# working.net
KiCad netlist of a schematic drawn in EAGLE
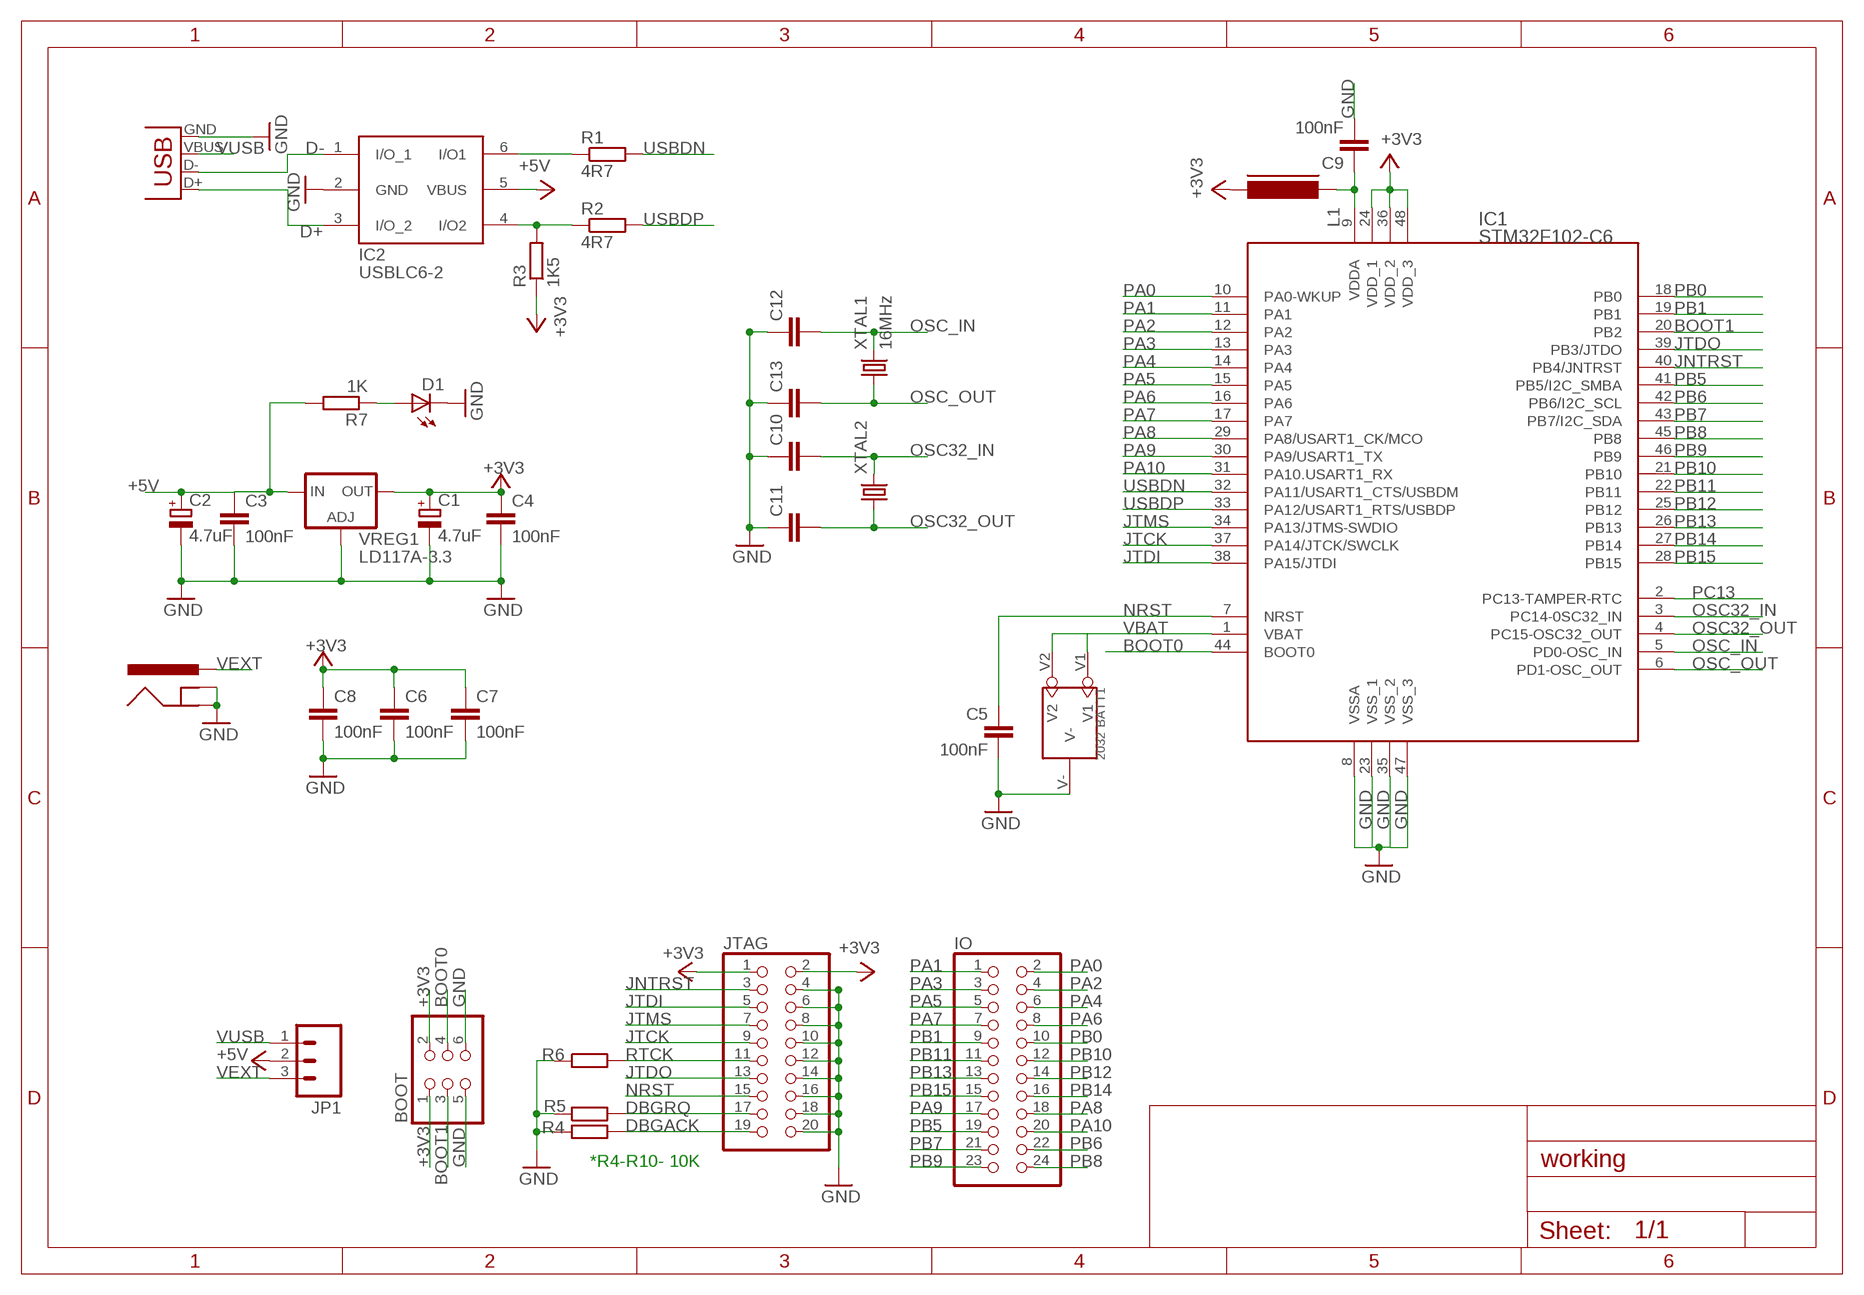
[diagram p0: schematic, sheet 1]

(export (version "E")
  (design (tool "Eeschema 10.0.6"))
  (components
    (comp (ref "BATT1")
      (value "2032")
      (footprint "eagle-import:2032")
      (libsource (lib "eagle-import") (part "2032"))
    )
    (comp (ref "BOOT")
      (value "PINHD-2X3")
      (footprint "eagle-import:2X03")
      (libsource (lib "eagle-import") (part "PINHD-2X3"))
    )
    (comp (ref "C1")
      (value "4.7uF")
      (footprint "eagle-import:SMC_A")
      (libsource (lib "eagle-import") (part "CAP_POLSMC_A"))
    )
    (comp (ref "C2")
      (value "4.7uF")
      (footprint "eagle-import:SMC_A")
      (libsource (lib "eagle-import") (part "CAP_POLSMC_A"))
    )
    (comp (ref "C3")
      (value "100nF")
      (footprint "eagle-import:C0805")
      (libsource (lib "eagle-import") (part "C-EUC0805"))
    )
    (comp (ref "C4")
      (value "100nF")
      (footprint "eagle-import:C0805")
      (libsource (lib "eagle-import") (part "C-EUC0805"))
    )
    (comp (ref "C5")
      (value "100nF")
      (footprint "eagle-import:C0805")
      (libsource (lib "eagle-import") (part "C-EUC0805"))
    )
    (comp (ref "C6")
      (value "100nF")
      (footprint "eagle-import:C0805")
      (libsource (lib "eagle-import") (part "C-EUC0805"))
    )
    (comp (ref "C7")
      (value "100nF")
      (footprint "eagle-import:C0805")
      (libsource (lib "eagle-import") (part "C-EUC0805"))
    )
    (comp (ref "C8")
      (value "100nF")
      (footprint "eagle-import:C0805")
      (libsource (lib "eagle-import") (part "C-EUC0805"))
    )
    (comp (ref "C9")
      (value "100nF")
      (footprint "eagle-import:C0805")
      (libsource (lib "eagle-import") (part "C-EUC0805"))
    )
    (comp (ref "C10")
      (value "CAPC805")
      (footprint "eagle-import:C805")
      (libsource (lib "eagle-import") (part "CAPC805"))
    )
    (comp (ref "C11")
      (value "CAPC805")
      (footprint "eagle-import:C805")
      (libsource (lib "eagle-import") (part "CAPC805"))
    )
    (comp (ref "C12")
      (value "CAPC805")
      (footprint "eagle-import:C805")
      (libsource (lib "eagle-import") (part "CAPC805"))
    )
    (comp (ref "C13")
      (value "CAPC805")
      (footprint "eagle-import:C805")
      (libsource (lib "eagle-import") (part "CAPC805"))
    )
    (comp (ref "D1")
      (value "LEDCHIPLED_0805")
      (footprint "eagle-import:CHIPLED_0805")
      (libsource (lib "eagle-import") (part "LEDCHIPLED_0805"))
    )
    (comp (ref "IC1")
      (value "STM32F102-C6")
      (footprint "eagle-import:LQFP48")
      (libsource (lib "eagle-import") (part "STM32"))
    )
    (comp (ref "IC2")
      (value "USBLC6-2")
      (footprint "eagle-import:SOT23-6L")
      (libsource (lib "eagle-import") (part "USBLC6-2"))
    )
    (comp (ref "IO")
      (value "PINHD-2X12")
      (footprint "eagle-import:2X12")
      (libsource (lib "eagle-import") (part "PINHD-2X12"))
    )
    (comp (ref "JP1")
      (value "M03PTH")
      (footprint "eagle-import:1X03")
      (libsource (lib "eagle-import") (part "M03PTH"))
    )
    (comp (ref "JTAG")
      (value "PINHD-2X10")
      (footprint "eagle-import:2X10")
      (libsource (lib "eagle-import") (part "PINHD-2X10"))
    )
    (comp (ref "L1")
      (value "FERRITE_BEAD805")
      (footprint "eagle-import:FB805")
      (libsource (lib "eagle-import") (part "FERRITE_BEAD805"))
    )
    (comp (ref "R1")
      (value "4R7")
      (footprint "eagle-import:R0805")
      (libsource (lib "eagle-import") (part "R-EU_R0805"))
    )
    (comp (ref "R2")
      (value "4R7")
      (footprint "eagle-import:R0805")
      (libsource (lib "eagle-import") (part "R-EU_R0805"))
    )
    (comp (ref "R3")
      (value "1K5")
      (footprint "eagle-import:R0805")
      (libsource (lib "eagle-import") (part "R-EU_R0805"))
    )
    (comp (ref "R4")
      (value "R-EU_R0805")
      (footprint "eagle-import:R0805")
      (libsource (lib "eagle-import") (part "R-EU_R0805"))
    )
    (comp (ref "R5")
      (value "R-EU_R0805")
      (footprint "eagle-import:R0805")
      (libsource (lib "eagle-import") (part "R-EU_R0805"))
    )
    (comp (ref "R6")
      (value "R-EU_R0805")
      (footprint "eagle-import:R0805")
      (libsource (lib "eagle-import") (part "R-EU_R0805"))
    )
    (comp (ref "R7")
      (value "1K")
      (footprint "eagle-import:R0805")
      (libsource (lib "eagle-import") (part "R-EU_R0805"))
    )
    (comp (ref "U$1")
      (value "POWER_JACKSMD")
      (footprint "eagle-import:POWER_JACK_SMD")
      (libsource (lib "eagle-import") (part "POWER_JACKSMD"))
    )
    (comp (ref "USB")
      (value "USBMINIB")
      (footprint "eagle-import:USB-MINIB")
      (libsource (lib "eagle-import") (part "USBMINIB"))
    )
    (comp (ref "VREG1")
      (value "LD117A-3.3")
      (footprint "eagle-import:SOT223")
      (libsource (lib "eagle-import") (part "LD117A?S12TR"))
    )
    (comp (ref "XTAL1")
      (value "16MHz")
      (footprint "eagle-import:HC49UP")
      (libsource (lib "eagle-import") (part "CRYSTALHC49UP"))
    )
    (comp (ref "XTAL2")
      (value "CRYSTALMM20SS")
      (footprint "eagle-import:MM20SS")
      (libsource (lib "eagle-import") (part "CRYSTALMM20SS"))
    )
  )
  (nets
    (net (code "1") (name "+3V3") (class "Default")
      (node (ref "BOOT") (pin "1") (pinfunction "1_1") (pintype "passive"))
      (node (ref "BOOT") (pin "2") (pinfunction "2_2") (pintype "passive"))
      (node (ref "C1") (pin "+") (pinfunction "+_+") (pintype "passive"))
      (node (ref "C4") (pin "1") (pinfunction "1_1") (pintype "passive"))
      (node (ref "C6") (pin "1") (pinfunction "1_1") (pintype "passive"))
      (node (ref "C7") (pin "1") (pinfunction "1_1") (pintype "passive"))
      (node (ref "C8") (pin "1") (pinfunction "1_1") (pintype "passive"))
      (node (ref "IC1") (pin "24") (pinfunction "VDD_1_24") (pintype "power_in"))
      (node (ref "IC1") (pin "36") (pinfunction "VDD_2_36") (pintype "power_in"))
      (node (ref "IC1") (pin "48") (pinfunction "VDD_3_48") (pintype "power_in"))
      (node (ref "JTAG") (pin "1") (pinfunction "1_1") (pintype "passive"))
      (node (ref "JTAG") (pin "2") (pinfunction "2_2") (pintype "passive"))
      (node (ref "L1") (pin "2") (pinfunction "2_2") (pintype "passive"))
      (node (ref "R3") (pin "1") (pinfunction "1_1") (pintype "passive"))
      (node (ref "VREG1") (pin "4") (pinfunction "OUT_4") (pintype "passive"))
    )
    (net (code "2") (name "+5V") (class "Default")
      (node (ref "C2") (pin "+") (pinfunction "+_+") (pintype "passive"))
      (node (ref "C3") (pin "1") (pinfunction "1_1") (pintype "passive"))
      (node (ref "IC2") (pin "5") (pinfunction "VBUS_5") (pintype "bidirectional"))
      (node (ref "JP1") (pin "2") (pinfunction "2_2") (pintype "passive"))
      (node (ref "R7") (pin "2") (pinfunction "2_2") (pintype "passive"))
      (node (ref "VREG1") (pin "3") (pinfunction "IN_3") (pintype "input"))
    )
    (net (code "3") (name "/BOOT0") (class "Default")
      (node (ref "BOOT") (pin "4") (pinfunction "4_4") (pintype "passive"))
      (node (ref "IC1") (pin "44") (pinfunction "BOOT0_44") (pintype "bidirectional"))
    )
    (net (code "4") (name "/BOOT1") (class "Default")
      (node (ref "BOOT") (pin "3") (pinfunction "3_3") (pintype "passive"))
      (node (ref "IC1") (pin "20") (pinfunction "PB2_20") (pintype "bidirectional"))
    )
    (net (code "5") (name "/D+") (class "Default")
      (node (ref "IC2") (pin "3") (pinfunction "I/O_2_3") (pintype "bidirectional"))
      (node (ref "USB") (pin "D+") (pinfunction "D+_D+") (pintype "bidirectional"))
    )
    (net (code "6") (name "/D-") (class "Default")
      (node (ref "IC2") (pin "1") (pinfunction "I/O_1_1") (pintype "bidirectional"))
      (node (ref "USB") (pin "D-") (pinfunction "D-_D-") (pintype "bidirectional"))
    )
    (net (code "7") (name "/DBGACK") (class "Default")
      (node (ref "JTAG") (pin "19") (pinfunction "19_19") (pintype "passive"))
      (node (ref "R4") (pin "2") (pinfunction "2_2") (pintype "passive"))
    )
    (net (code "8") (name "/DBGRQ") (class "Default")
      (node (ref "JTAG") (pin "17") (pinfunction "17_17") (pintype "passive"))
      (node (ref "R5") (pin "2") (pinfunction "2_2") (pintype "passive"))
    )
    (net (code "9") (name "/JNTRST") (class "Default")
      (node (ref "IC1") (pin "40") (pinfunction "PB4/JNTRST_40") (pintype "bidirectional"))
      (node (ref "JTAG") (pin "3") (pinfunction "3_3") (pintype "passive"))
    )
    (net (code "10") (name "/JTCK") (class "Default")
      (node (ref "IC1") (pin "37") (pinfunction "PA14/JTCK/SWCLK_37") (pintype "bidirectional"))
      (node (ref "JTAG") (pin "9") (pinfunction "9_9") (pintype "passive"))
    )
    (net (code "11") (name "/JTDI") (class "Default")
      (node (ref "IC1") (pin "38") (pinfunction "PA15/JTDI_38") (pintype "bidirectional"))
      (node (ref "JTAG") (pin "5") (pinfunction "5_5") (pintype "passive"))
    )
    (net (code "12") (name "/JTDO") (class "Default")
      (node (ref "IC1") (pin "39") (pinfunction "PB3/JTDO_39") (pintype "bidirectional"))
      (node (ref "JTAG") (pin "13") (pinfunction "13_13") (pintype "passive"))
    )
    (net (code "13") (name "/JTMS") (class "Default")
      (node (ref "IC1") (pin "34") (pinfunction "PA13/JTMS-SWDIO_34") (pintype "bidirectional"))
      (node (ref "JTAG") (pin "7") (pinfunction "7_7") (pintype "passive"))
    )
    (net (code "14") (name "/NRST") (class "Default")
      (node (ref "C5") (pin "1") (pinfunction "1_1") (pintype "passive"))
      (node (ref "IC1") (pin "7") (pinfunction "NRST_7") (pintype "bidirectional"))
      (node (ref "JTAG") (pin "15") (pinfunction "15_15") (pintype "passive"))
    )
    (net (code "15") (name "/OSC32_IN") (class "Default")
      (node (ref "C10") (pin "2") (pinfunction "2_2") (pintype "passive"))
      (node (ref "IC1") (pin "3") (pinfunction "PC14-0SC32_IN_3") (pintype "bidirectional"))
      (node (ref "XTAL2") (pin "4") (pinfunction "2_4") (pintype "passive"))
    )
    (net (code "16") (name "/OSC32_OUT") (class "Default")
      (node (ref "C11") (pin "2") (pinfunction "2_2") (pintype "passive"))
      (node (ref "IC1") (pin "4") (pinfunction "PC15-OSC32_OUT_4") (pintype "bidirectional"))
      (node (ref "XTAL2") (pin "1") (pinfunction "1_1") (pintype "passive"))
    )
    (net (code "17") (name "/OSC_IN") (class "Default")
      (node (ref "C12") (pin "2") (pinfunction "2_2") (pintype "passive"))
      (node (ref "IC1") (pin "5") (pinfunction "PD0-OSC_IN_5") (pintype "bidirectional"))
      (node (ref "XTAL1") (pin "2") (pinfunction "2_2") (pintype "passive"))
    )
    (net (code "18") (name "/OSC_OUT") (class "Default")
      (node (ref "C13") (pin "2") (pinfunction "2_2") (pintype "passive"))
      (node (ref "IC1") (pin "6") (pinfunction "PD1-OSC_OUT_6") (pintype "bidirectional"))
      (node (ref "XTAL1") (pin "1") (pinfunction "1_1") (pintype "passive"))
    )
    (net (code "19") (name "/PA0") (class "Default")
      (node (ref "IC1") (pin "10") (pinfunction "PA0-WKUP_10") (pintype "bidirectional"))
      (node (ref "IO") (pin "2") (pinfunction "2_2") (pintype "passive"))
    )
    (net (code "20") (name "/PA1") (class "Default")
      (node (ref "IC1") (pin "11") (pinfunction "PA1_11") (pintype "bidirectional"))
      (node (ref "IO") (pin "1") (pinfunction "1_1") (pintype "passive"))
    )
    (net (code "21") (name "/PA2") (class "Default")
      (node (ref "IC1") (pin "12") (pinfunction "PA2_12") (pintype "bidirectional"))
      (node (ref "IO") (pin "4") (pinfunction "4_4") (pintype "passive"))
    )
    (net (code "22") (name "/PA3") (class "Default")
      (node (ref "IC1") (pin "13") (pinfunction "PA3_13") (pintype "bidirectional"))
      (node (ref "IO") (pin "3") (pinfunction "3_3") (pintype "passive"))
    )
    (net (code "23") (name "/PA4") (class "Default")
      (node (ref "IC1") (pin "14") (pinfunction "PA4_14") (pintype "bidirectional"))
      (node (ref "IO") (pin "6") (pinfunction "6_6") (pintype "passive"))
    )
    (net (code "24") (name "/PA5") (class "Default")
      (node (ref "IC1") (pin "15") (pinfunction "PA5_15") (pintype "bidirectional"))
      (node (ref "IO") (pin "5") (pinfunction "5_5") (pintype "passive"))
    )
    (net (code "25") (name "/PA6") (class "Default")
      (node (ref "IC1") (pin "16") (pinfunction "PA6_16") (pintype "bidirectional"))
      (node (ref "IO") (pin "8") (pinfunction "8_8") (pintype "passive"))
    )
    (net (code "26") (name "/PA7") (class "Default")
      (node (ref "IC1") (pin "17") (pinfunction "PA7_17") (pintype "bidirectional"))
      (node (ref "IO") (pin "7") (pinfunction "7_7") (pintype "passive"))
    )
    (net (code "27") (name "/PA8") (class "Default")
      (node (ref "IC1") (pin "29") (pinfunction "PA8/USART1_CK/MCO_29") (pintype "bidirectional"))
      (node (ref "IO") (pin "18") (pinfunction "18_18") (pintype "passive"))
    )
    (net (code "28") (name "/PA9") (class "Default")
      (node (ref "IC1") (pin "30") (pinfunction "PA9/USART1_TX_30") (pintype "bidirectional"))
      (node (ref "IO") (pin "17") (pinfunction "17_17") (pintype "passive"))
    )
    (net (code "29") (name "/PA10") (class "Default")
      (node (ref "IC1") (pin "31") (pinfunction "PA10.USART1_RX_31") (pintype "bidirectional"))
      (node (ref "IO") (pin "20") (pinfunction "20_20") (pintype "passive"))
    )
    (net (code "30") (name "/PB0") (class "Default")
      (node (ref "IC1") (pin "18") (pinfunction "PB0_18") (pintype "bidirectional"))
      (node (ref "IO") (pin "10") (pinfunction "10_10") (pintype "passive"))
    )
    (net (code "31") (name "/PB1") (class "Default")
      (node (ref "IC1") (pin "19") (pinfunction "PB1_19") (pintype "bidirectional"))
      (node (ref "IO") (pin "9") (pinfunction "9_9") (pintype "passive"))
    )
    (net (code "32") (name "/PB5") (class "Default")
      (node (ref "IC1") (pin "41") (pinfunction "PB5/I2C_SMBA_41") (pintype "bidirectional"))
      (node (ref "IO") (pin "19") (pinfunction "19_19") (pintype "passive"))
    )
    (net (code "33") (name "/PB6") (class "Default")
      (node (ref "IC1") (pin "42") (pinfunction "PB6/I2C_SCL_42") (pintype "bidirectional"))
      (node (ref "IO") (pin "22") (pinfunction "22_22") (pintype "passive"))
    )
    (net (code "34") (name "/PB7") (class "Default")
      (node (ref "IC1") (pin "43") (pinfunction "PB7/I2C_SDA_43") (pintype "bidirectional"))
      (node (ref "IO") (pin "21") (pinfunction "21_21") (pintype "passive"))
    )
    (net (code "35") (name "/PB8") (class "Default")
      (node (ref "IC1") (pin "45") (pinfunction "PB8_45") (pintype "bidirectional"))
      (node (ref "IO") (pin "24") (pinfunction "24_24") (pintype "passive"))
    )
    (net (code "36") (name "/PB9") (class "Default")
      (node (ref "IC1") (pin "46") (pinfunction "PB9_46") (pintype "bidirectional"))
      (node (ref "IO") (pin "23") (pinfunction "23_23") (pintype "passive"))
    )
    (net (code "37") (name "/PB10") (class "Default")
      (node (ref "IC1") (pin "21") (pinfunction "PB10_21") (pintype "bidirectional"))
      (node (ref "IO") (pin "12") (pinfunction "12_12") (pintype "passive"))
    )
    (net (code "38") (name "/PB11") (class "Default")
      (node (ref "IC1") (pin "22") (pinfunction "PB11_22") (pintype "bidirectional"))
      (node (ref "IO") (pin "11") (pinfunction "11_11") (pintype "passive"))
    )
    (net (code "39") (name "/PB12") (class "Default")
      (node (ref "IC1") (pin "25") (pinfunction "PB12_25") (pintype "bidirectional"))
      (node (ref "IO") (pin "14") (pinfunction "14_14") (pintype "passive"))
    )
    (net (code "40") (name "/PB13") (class "Default")
      (node (ref "IC1") (pin "26") (pinfunction "PB13_26") (pintype "bidirectional"))
      (node (ref "IO") (pin "13") (pinfunction "13_13") (pintype "passive"))
    )
    (net (code "41") (name "/PB14") (class "Default")
      (node (ref "IC1") (pin "27") (pinfunction "PB14_27") (pintype "bidirectional"))
      (node (ref "IO") (pin "16") (pinfunction "16_16") (pintype "passive"))
    )
    (net (code "42") (name "/PB15") (class "Default")
      (node (ref "IC1") (pin "28") (pinfunction "PB15_28") (pintype "bidirectional"))
      (node (ref "IO") (pin "15") (pinfunction "15_15") (pintype "passive"))
    )
    (net (code "43") (name "/PC13") (class "Default")
      (node (ref "IC1") (pin "2") (pinfunction "PC13-TAMPER-RTC_2") (pintype "bidirectional"))
    )
    (net (code "44") (name "/RTCK") (class "Default")
      (node (ref "JTAG") (pin "11") (pinfunction "11_11") (pintype "passive"))
      (node (ref "R6") (pin "2") (pinfunction "2_2") (pintype "passive"))
    )
    (net (code "45") (name "/USBDN") (class "Default")
      (node (ref "IC1") (pin "32") (pinfunction "PA11/USART1_CTS/USBDM_32") (pintype "bidirectional"))
      (node (ref "R1") (pin "2") (pinfunction "2_2") (pintype "passive"))
    )
    (net (code "46") (name "/USBDP") (class "Default")
      (node (ref "IC1") (pin "33") (pinfunction "PA12/USART1_RTS/USBDP_33") (pintype "bidirectional"))
      (node (ref "R2") (pin "2") (pinfunction "2_2") (pintype "passive"))
    )
    (net (code "47") (name "/VBAT") (class "Default")
      (node (ref "BATT1") (pin "V1") (pinfunction "V1_V1") (pintype "bidirectional"))
      (node (ref "BATT1") (pin "V2") (pinfunction "V2_V2") (pintype "bidirectional"))
      (node (ref "IC1") (pin "1") (pinfunction "VBAT_1") (pintype "bidirectional"))
    )
    (net (code "48") (name "/VEXT") (class "Default")
      (node (ref "JP1") (pin "3") (pinfunction "3_3") (pintype "passive"))
      (node (ref "U$1") (pin "VIN0") (pinfunction "PWR_VIN0") (pintype "bidirectional"))
    )
    (net (code "49") (name "/VUSB") (class "Default")
      (node (ref "JP1") (pin "1") (pinfunction "1_1") (pintype "passive"))
      (node (ref "USB") (pin "VBUS") (pinfunction "VBUS_VBUS") (pintype "bidirectional"))
    )
    (net (code "50") (name "GND") (class "Default")
      (node (ref "BATT1") (pin "V-") (pinfunction "V-_V-") (pintype "bidirectional"))
      (node (ref "BOOT") (pin "5") (pinfunction "5_5") (pintype "passive"))
      (node (ref "BOOT") (pin "6") (pinfunction "6_6") (pintype "passive"))
      (node (ref "C1") (pin "-") (pinfunction "-_-") (pintype "passive"))
      (node (ref "C10") (pin "1") (pinfunction "1_1") (pintype "passive"))
      (node (ref "C11") (pin "1") (pinfunction "1_1") (pintype "passive"))
      (node (ref "C12") (pin "1") (pinfunction "1_1") (pintype "passive"))
      (node (ref "C13") (pin "1") (pinfunction "1_1") (pintype "passive"))
      (node (ref "C2") (pin "-") (pinfunction "-_-") (pintype "passive"))
      (node (ref "C3") (pin "2") (pinfunction "2_2") (pintype "passive"))
      (node (ref "C4") (pin "2") (pinfunction "2_2") (pintype "passive"))
      (node (ref "C5") (pin "2") (pinfunction "2_2") (pintype "passive"))
      (node (ref "C6") (pin "2") (pinfunction "2_2") (pintype "passive"))
      (node (ref "C7") (pin "2") (pinfunction "2_2") (pintype "passive"))
      (node (ref "C8") (pin "2") (pinfunction "2_2") (pintype "passive"))
      (node (ref "C9") (pin "2") (pinfunction "2_2") (pintype "passive"))
      (node (ref "D1") (pin "C") (pinfunction "C_C") (pintype "passive"))
      (node (ref "IC1") (pin "23") (pinfunction "VSS_1_23") (pintype "power_in"))
      (node (ref "IC1") (pin "35") (pinfunction "VSS_2_35") (pintype "power_in"))
      (node (ref "IC1") (pin "47") (pinfunction "VSS_3_47") (pintype "power_in"))
      (node (ref "IC1") (pin "8") (pinfunction "VSSA_8") (pintype "power_in"))
      (node (ref "IC2") (pin "2") (pinfunction "GND_2") (pintype "bidirectional"))
      (node (ref "JTAG") (pin "10") (pinfunction "10_10") (pintype "passive"))
      (node (ref "JTAG") (pin "12") (pinfunction "12_12") (pintype "passive"))
      (node (ref "JTAG") (pin "14") (pinfunction "14_14") (pintype "passive"))
      (node (ref "JTAG") (pin "16") (pinfunction "16_16") (pintype "passive"))
      (node (ref "JTAG") (pin "18") (pinfunction "18_18") (pintype "passive"))
      (node (ref "JTAG") (pin "20") (pinfunction "20_20") (pintype "passive"))
      (node (ref "JTAG") (pin "4") (pinfunction "4_4") (pintype "passive"))
      (node (ref "JTAG") (pin "6") (pinfunction "6_6") (pintype "passive"))
      (node (ref "JTAG") (pin "8") (pinfunction "8_8") (pintype "passive"))
      (node (ref "R4") (pin "1") (pinfunction "1_1") (pintype "passive"))
      (node (ref "R5") (pin "1") (pinfunction "1_1") (pintype "passive"))
      (node (ref "R6") (pin "1") (pinfunction "1_1") (pintype "passive"))
      (node (ref "U$1") (pin "GND") (pinfunction "GND_GND") (pintype "bidirectional"))
      (node (ref "U$1") (pin "P$4") (pinfunction "GND_P$4") (pintype "bidirectional"))
      (node (ref "USB") (pin "GND") (pinfunction "GND_GND") (pintype "bidirectional"))
      (node (ref "VREG1") (pin "1") (pinfunction "ADJ_1") (pintype "input"))
    )
    (net (code "51") (name "Net-(D1-PadA)") (class "Default")
      (node (ref "D1") (pin "A") (pinfunction "A_A") (pintype "passive"))
      (node (ref "R7") (pin "1") (pinfunction "1_1") (pintype "passive"))
    )
    (net (code "52") (name "Net-(IC1-VDDA)") (class "Default")
      (node (ref "C9") (pin "1") (pinfunction "1_1") (pintype "passive"))
      (node (ref "IC1") (pin "9") (pinfunction "VDDA_9") (pintype "power_in"))
      (node (ref "L1") (pin "1") (pinfunction "1_1") (pintype "passive"))
    )
    (net (code "53") (name "Net-(IC2-I{slash}O1)") (class "Default")
      (node (ref "IC2") (pin "6") (pinfunction "I/O1_6") (pintype "bidirectional"))
      (node (ref "R1") (pin "1") (pinfunction "1_1") (pintype "passive"))
    )
    (net (code "54") (name "Net-(IC2-I{slash}O2)") (class "Default")
      (node (ref "IC2") (pin "4") (pinfunction "I/O2_4") (pintype "bidirectional"))
      (node (ref "R2") (pin "1") (pinfunction "1_1") (pintype "passive"))
      (node (ref "R3") (pin "2") (pinfunction "2_2") (pintype "passive"))
    )
  )
)
